# wordClock.net
KiCad netlist of a schematic drawn in EAGLE
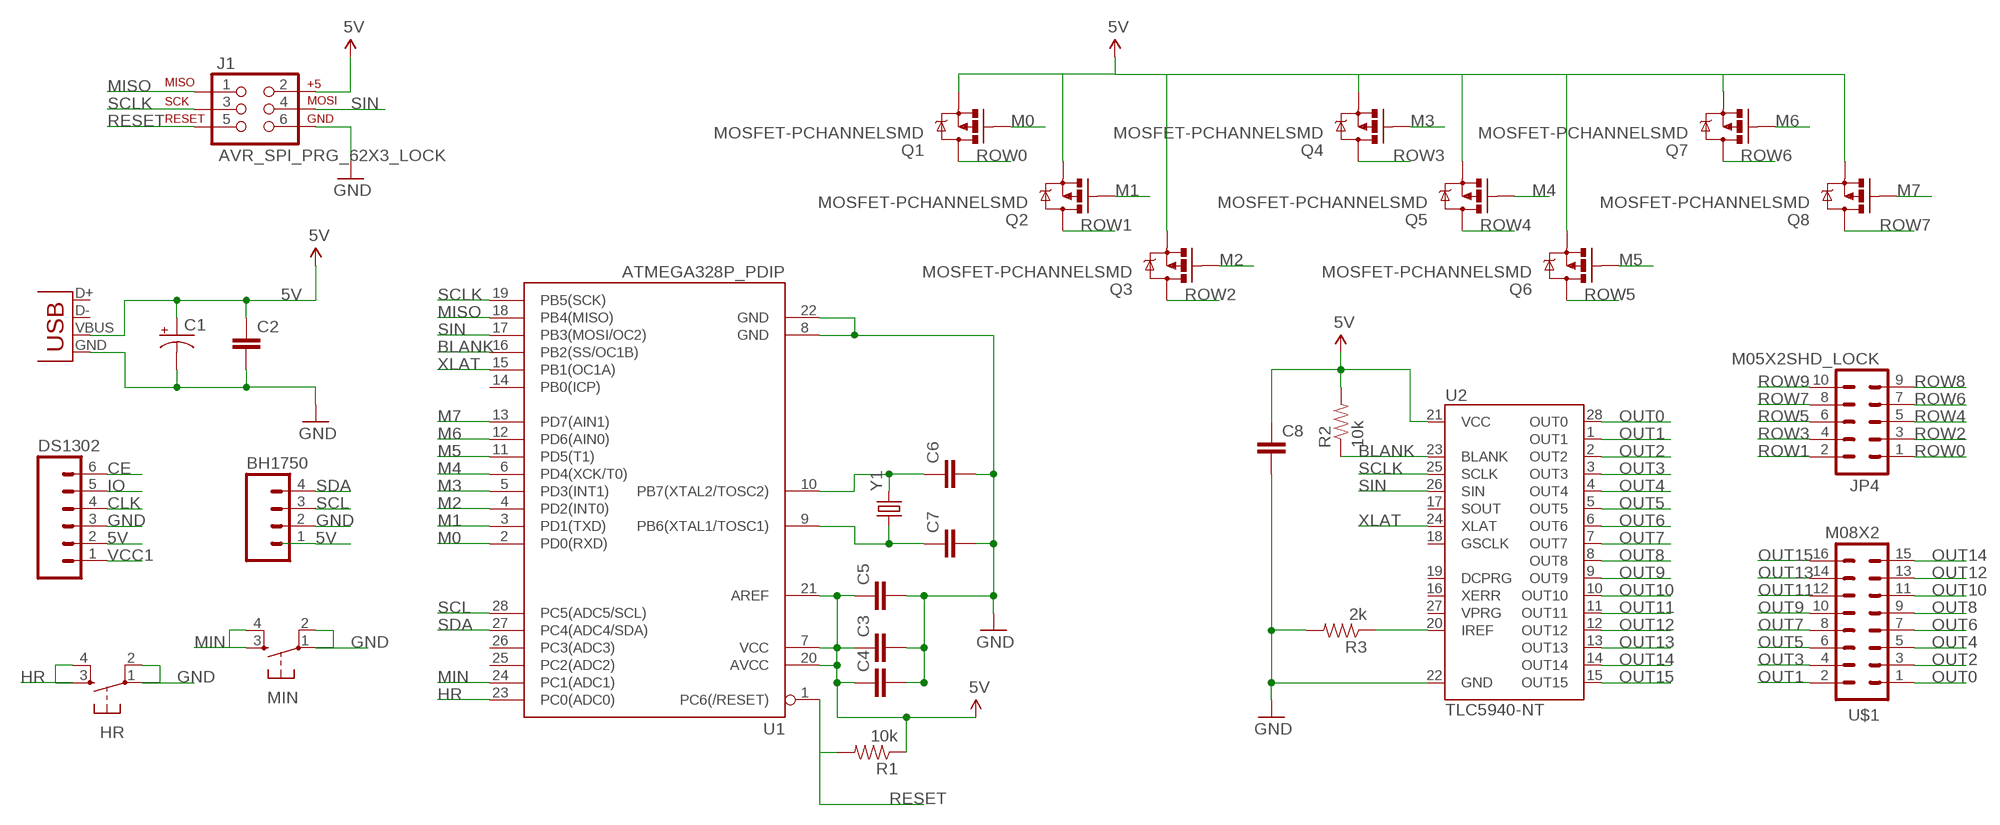
[diagram p0: schematic, sheet 1]

(export (version "E")
  (design (tool "Eeschema 10.0.6"))
  (components
    (comp (ref "BH1750")
      (value "M04LOCK")
      (footprint "eagle-import:1X04_LOCK")
      (libsource (lib "eagle-import") (part "M04LOCK"))
    )
    (comp (ref "C1")
      (value "CAP_POLD")
      (footprint "eagle-import:PANASONIC_D")
      (libsource (lib "eagle-import") (part "CAP_POLD"))
    )
    (comp (ref "C2")
      (value "CAP0805")
      (footprint "eagle-import:0805")
      (libsource (lib "eagle-import") (part "CAP0805"))
    )
    (comp (ref "C3")
      (value "CAP0805")
      (footprint "eagle-import:0805")
      (libsource (lib "eagle-import") (part "CAP0805"))
    )
    (comp (ref "C4")
      (value "CAP0805")
      (footprint "eagle-import:0805")
      (libsource (lib "eagle-import") (part "CAP0805"))
    )
    (comp (ref "C5")
      (value "CAP0805")
      (footprint "eagle-import:0805")
      (libsource (lib "eagle-import") (part "CAP0805"))
    )
    (comp (ref "C6")
      (value "CAP0805")
      (footprint "eagle-import:0805")
      (libsource (lib "eagle-import") (part "CAP0805"))
    )
    (comp (ref "C7")
      (value "CAP0805")
      (footprint "eagle-import:0805")
      (libsource (lib "eagle-import") (part "CAP0805"))
    )
    (comp (ref "C8")
      (value "CAP0805")
      (footprint "eagle-import:0805")
      (libsource (lib "eagle-import") (part "CAP0805"))
    )
    (comp (ref "DS1302")
      (value "M06LOCK")
      (footprint "eagle-import:1X06_LOCK")
      (libsource (lib "eagle-import") (part "M06LOCK"))
    )
    (comp (ref "HR")
      (value "TAC_SWITCHPTH")
      (footprint "eagle-import:TACTILE-PTH")
      (libsource (lib "eagle-import") (part "TAC_SWITCHPTH"))
    )
    (comp (ref "J1")
      (value "AVR_SPI_PRG_62X3_LOCK")
      (footprint "eagle-import:2X3_LOCK")
      (libsource (lib "eagle-import") (part "AVR_SPI_PRG_62X3_LOCK"))
    )
    (comp (ref "JP1")
      (value "USBPTH-VERTICAL")
      (footprint "eagle-import:USB-B-PTH-VERTICAL")
      (libsource (lib "eagle-import") (part "USBPTH-VERTICAL"))
    )
    (comp (ref "JP4")
      (value "M05X2SHD_LOCK")
      (footprint "eagle-import:2X5-SHROUDED_LOCK")
      (libsource (lib "eagle-import") (part "M05X2SHD_LOCK"))
    )
    (comp (ref "MIN")
      (value "TAC_SWITCHPTH")
      (footprint "eagle-import:TACTILE-PTH")
      (libsource (lib "eagle-import") (part "TAC_SWITCHPTH"))
    )
    (comp (ref "Q1")
      (value "MOSFET-PCHANNELSMD")
      (footprint "eagle-import:SOT23-3")
      (libsource (lib "eagle-import") (part "MOSFET-PCHANNELSMD"))
    )
    (comp (ref "Q2")
      (value "MOSFET-PCHANNELSMD")
      (footprint "eagle-import:SOT23-3")
      (libsource (lib "eagle-import") (part "MOSFET-PCHANNELSMD"))
    )
    (comp (ref "Q3")
      (value "MOSFET-PCHANNELSMD")
      (footprint "eagle-import:SOT23-3")
      (libsource (lib "eagle-import") (part "MOSFET-PCHANNELSMD"))
    )
    (comp (ref "Q4")
      (value "MOSFET-PCHANNELSMD")
      (footprint "eagle-import:SOT23-3")
      (libsource (lib "eagle-import") (part "MOSFET-PCHANNELSMD"))
    )
    (comp (ref "Q5")
      (value "MOSFET-PCHANNELSMD")
      (footprint "eagle-import:SOT23-3")
      (libsource (lib "eagle-import") (part "MOSFET-PCHANNELSMD"))
    )
    (comp (ref "Q6")
      (value "MOSFET-PCHANNELSMD")
      (footprint "eagle-import:SOT23-3")
      (libsource (lib "eagle-import") (part "MOSFET-PCHANNELSMD"))
    )
    (comp (ref "Q7")
      (value "MOSFET-PCHANNELSMD")
      (footprint "eagle-import:SOT23-3")
      (libsource (lib "eagle-import") (part "MOSFET-PCHANNELSMD"))
    )
    (comp (ref "Q8")
      (value "MOSFET-PCHANNELSMD")
      (footprint "eagle-import:SOT23-3")
      (libsource (lib "eagle-import") (part "MOSFET-PCHANNELSMD"))
    )
    (comp (ref "R1")
      (value "10k")
      (footprint "eagle-import:0805")
      (libsource (lib "eagle-import") (part "RESISTOR0805-RES"))
    )
    (comp (ref "R2")
      (value "10k")
      (footprint "eagle-import:0805")
      (libsource (lib "eagle-import") (part "RESISTOR0805-RES"))
    )
    (comp (ref "R3")
      (value "2k")
      (footprint "eagle-import:0805")
      (libsource (lib "eagle-import") (part "RESISTOR0805-RES"))
    )
    (comp (ref "U$1")
      (value "M08X2")
      (footprint "eagle-import:2X8")
      (libsource (lib "eagle-import") (part "M08X2"))
    )
    (comp (ref "U1")
      (value "ATMEGA328P_PDIP")
      (footprint "eagle-import:DIL28-3")
      (libsource (lib "eagle-import") (part "ATMEGA328P_PDIP"))
    )
    (comp (ref "U2")
      (value "TLC5940-NT")
      (footprint "eagle-import:DIL28-3")
      (libsource (lib "eagle-import") (part "TLC5940-NT"))
    )
    (comp (ref "Y1")
      (value "CRYSTALSMD")
      (footprint "eagle-import:HC49UP")
      (libsource (lib "eagle-import") (part "CRYSTALSMD"))
    )
  )
  (nets
    (net (code "1") (name "/BLANK") (class "Default")
      (node (ref "R2") (pin "1") (pinfunction "1_1") (pintype "passive"))
      (node (ref "U1") (pin "16") (pinfunction "PB2(SS/OC1B)_16") (pintype "bidirectional"))
      (node (ref "U2") (pin "23") (pinfunction "BLANK_23") (pintype "bidirectional"))
    )
    (net (code "2") (name "/CE") (class "Default")
      (node (ref "DS1302") (pin "6") (pinfunction "6_6") (pintype "passive"))
    )
    (net (code "3") (name "/CLK") (class "Default")
      (node (ref "DS1302") (pin "4") (pinfunction "4_4") (pintype "passive"))
    )
    (net (code "4") (name "/HR") (class "Default")
      (node (ref "HR") (pin "3") (pinfunction "3_3") (pintype "passive"))
      (node (ref "HR") (pin "4") (pinfunction "4_4") (pintype "passive"))
      (node (ref "U1") (pin "23") (pinfunction "PC0(ADC0)_23") (pintype "bidirectional"))
    )
    (net (code "5") (name "/IO") (class "Default")
      (node (ref "DS1302") (pin "5") (pinfunction "5_5") (pintype "passive"))
    )
    (net (code "6") (name "/M0") (class "Default")
      (node (ref "Q1") (pin "1") (pinfunction "G_1") (pintype "passive"))
      (node (ref "U1") (pin "2") (pinfunction "PD0(RXD)_2") (pintype "bidirectional"))
    )
    (net (code "7") (name "/M1") (class "Default")
      (node (ref "Q2") (pin "1") (pinfunction "G_1") (pintype "passive"))
      (node (ref "U1") (pin "3") (pinfunction "PD1(TXD)_3") (pintype "bidirectional"))
    )
    (net (code "8") (name "/M2") (class "Default")
      (node (ref "Q3") (pin "1") (pinfunction "G_1") (pintype "passive"))
      (node (ref "U1") (pin "4") (pinfunction "PD2(INT0)_4") (pintype "bidirectional"))
    )
    (net (code "9") (name "/M3") (class "Default")
      (node (ref "Q4") (pin "1") (pinfunction "G_1") (pintype "passive"))
      (node (ref "U1") (pin "5") (pinfunction "PD3(INT1)_5") (pintype "bidirectional"))
    )
    (net (code "10") (name "/M4") (class "Default")
      (node (ref "Q5") (pin "1") (pinfunction "G_1") (pintype "passive"))
      (node (ref "U1") (pin "6") (pinfunction "PD4(XCK/T0)_6") (pintype "bidirectional"))
    )
    (net (code "11") (name "/M5") (class "Default")
      (node (ref "Q6") (pin "1") (pinfunction "G_1") (pintype "passive"))
      (node (ref "U1") (pin "11") (pinfunction "PD5(T1)_11") (pintype "bidirectional"))
    )
    (net (code "12") (name "/M6") (class "Default")
      (node (ref "Q7") (pin "1") (pinfunction "G_1") (pintype "passive"))
      (node (ref "U1") (pin "12") (pinfunction "PD6(AIN0)_12") (pintype "bidirectional"))
    )
    (net (code "13") (name "/M7") (class "Default")
      (node (ref "Q8") (pin "1") (pinfunction "G_1") (pintype "passive"))
      (node (ref "U1") (pin "13") (pinfunction "PD7(AIN1)_13") (pintype "bidirectional"))
    )
    (net (code "14") (name "/MIN") (class "Default")
      (node (ref "MIN") (pin "3") (pinfunction "3_3") (pintype "passive"))
      (node (ref "MIN") (pin "4") (pinfunction "4_4") (pintype "passive"))
      (node (ref "U1") (pin "24") (pinfunction "PC1(ADC1)_24") (pintype "bidirectional"))
    )
    (net (code "15") (name "/MISO") (class "Default")
      (node (ref "J1") (pin "1") (pinfunction "1_1") (pintype "passive"))
      (node (ref "U1") (pin "18") (pinfunction "PB4(MISO)_18") (pintype "bidirectional"))
    )
    (net (code "16") (name "/OUT0") (class "Default")
      (node (ref "U$1") (pin "1") (pinfunction "1_1") (pintype "passive"))
      (node (ref "U2") (pin "28") (pinfunction "OUT0_28") (pintype "bidirectional"))
    )
    (net (code "17") (name "/OUT1") (class "Default")
      (node (ref "U$1") (pin "2") (pinfunction "2_2") (pintype "passive"))
      (node (ref "U2") (pin "1") (pinfunction "OUT1_1") (pintype "bidirectional"))
    )
    (net (code "18") (name "/OUT2") (class "Default")
      (node (ref "U$1") (pin "3") (pinfunction "3_3") (pintype "passive"))
      (node (ref "U2") (pin "2") (pinfunction "OUT2_2") (pintype "bidirectional"))
    )
    (net (code "19") (name "/OUT3") (class "Default")
      (node (ref "U$1") (pin "4") (pinfunction "4_4") (pintype "passive"))
      (node (ref "U2") (pin "3") (pinfunction "OUT3_3") (pintype "bidirectional"))
    )
    (net (code "20") (name "/OUT4") (class "Default")
      (node (ref "U$1") (pin "5") (pinfunction "5_5") (pintype "passive"))
      (node (ref "U2") (pin "4") (pinfunction "OUT4_4") (pintype "bidirectional"))
    )
    (net (code "21") (name "/OUT5") (class "Default")
      (node (ref "U$1") (pin "6") (pinfunction "6_6") (pintype "passive"))
      (node (ref "U2") (pin "5") (pinfunction "OUT5_5") (pintype "bidirectional"))
    )
    (net (code "22") (name "/OUT6") (class "Default")
      (node (ref "U$1") (pin "7") (pinfunction "7_7") (pintype "passive"))
      (node (ref "U2") (pin "6") (pinfunction "OUT6_6") (pintype "bidirectional"))
    )
    (net (code "23") (name "/OUT7") (class "Default")
      (node (ref "U$1") (pin "8") (pinfunction "8_8") (pintype "passive"))
      (node (ref "U2") (pin "7") (pinfunction "OUT7_7") (pintype "bidirectional"))
    )
    (net (code "24") (name "/OUT8") (class "Default")
      (node (ref "U$1") (pin "9") (pinfunction "9_9") (pintype "passive"))
      (node (ref "U2") (pin "8") (pinfunction "OUT8_8") (pintype "bidirectional"))
    )
    (net (code "25") (name "/OUT9") (class "Default")
      (node (ref "U$1") (pin "10") (pinfunction "10_10") (pintype "passive"))
      (node (ref "U2") (pin "9") (pinfunction "OUT9_9") (pintype "bidirectional"))
    )
    (net (code "26") (name "/OUT10") (class "Default")
      (node (ref "U$1") (pin "11") (pinfunction "11_11") (pintype "passive"))
      (node (ref "U2") (pin "10") (pinfunction "OUT10_10") (pintype "bidirectional"))
    )
    (net (code "27") (name "/OUT11") (class "Default")
      (node (ref "U$1") (pin "12") (pinfunction "12_12") (pintype "passive"))
      (node (ref "U2") (pin "11") (pinfunction "OUT11_11") (pintype "bidirectional"))
    )
    (net (code "28") (name "/OUT12") (class "Default")
      (node (ref "U$1") (pin "13") (pinfunction "13_13") (pintype "passive"))
      (node (ref "U2") (pin "12") (pinfunction "OUT12_12") (pintype "bidirectional"))
    )
    (net (code "29") (name "/OUT13") (class "Default")
      (node (ref "U$1") (pin "14") (pinfunction "14_14") (pintype "passive"))
      (node (ref "U2") (pin "13") (pinfunction "OUT13_13") (pintype "bidirectional"))
    )
    (net (code "30") (name "/OUT14") (class "Default")
      (node (ref "U$1") (pin "15") (pinfunction "15_15") (pintype "passive"))
      (node (ref "U2") (pin "14") (pinfunction "OUT14_14") (pintype "bidirectional"))
    )
    (net (code "31") (name "/OUT15") (class "Default")
      (node (ref "U$1") (pin "16") (pinfunction "16_16") (pintype "passive"))
      (node (ref "U2") (pin "15") (pinfunction "OUT15_15") (pintype "bidirectional"))
    )
    (net (code "32") (name "/RESET") (class "Default")
      (node (ref "J1") (pin "5") (pinfunction "5_5") (pintype "passive"))
      (node (ref "R1") (pin "2") (pinfunction "2_2") (pintype "passive"))
      (node (ref "U1") (pin "1") (pinfunction "PC6(/RESET)_1") (pintype "bidirectional"))
    )
    (net (code "33") (name "/ROW0") (class "Default")
      (node (ref "JP4") (pin "1") (pinfunction "1_1") (pintype "passive"))
      (node (ref "Q1") (pin "3") (pinfunction "D_3") (pintype "passive"))
    )
    (net (code "34") (name "/ROW1") (class "Default")
      (node (ref "JP4") (pin "2") (pinfunction "2_2") (pintype "passive"))
      (node (ref "Q2") (pin "3") (pinfunction "D_3") (pintype "passive"))
    )
    (net (code "35") (name "/ROW2") (class "Default")
      (node (ref "JP4") (pin "3") (pinfunction "3_3") (pintype "passive"))
      (node (ref "Q3") (pin "3") (pinfunction "D_3") (pintype "passive"))
    )
    (net (code "36") (name "/ROW3") (class "Default")
      (node (ref "JP4") (pin "4") (pinfunction "4_4") (pintype "passive"))
      (node (ref "Q4") (pin "3") (pinfunction "D_3") (pintype "passive"))
    )
    (net (code "37") (name "/ROW4") (class "Default")
      (node (ref "JP4") (pin "5") (pinfunction "5_5") (pintype "passive"))
      (node (ref "Q5") (pin "3") (pinfunction "D_3") (pintype "passive"))
    )
    (net (code "38") (name "/ROW5") (class "Default")
      (node (ref "JP4") (pin "6") (pinfunction "6_6") (pintype "passive"))
      (node (ref "Q6") (pin "3") (pinfunction "D_3") (pintype "passive"))
    )
    (net (code "39") (name "/ROW6") (class "Default")
      (node (ref "JP4") (pin "7") (pinfunction "7_7") (pintype "passive"))
      (node (ref "Q7") (pin "3") (pinfunction "D_3") (pintype "passive"))
    )
    (net (code "40") (name "/ROW7") (class "Default")
      (node (ref "JP4") (pin "8") (pinfunction "8_8") (pintype "passive"))
      (node (ref "Q8") (pin "3") (pinfunction "D_3") (pintype "passive"))
    )
    (net (code "41") (name "/ROW8") (class "Default")
      (node (ref "JP4") (pin "9") (pinfunction "9_9") (pintype "passive"))
    )
    (net (code "42") (name "/ROW9") (class "Default")
      (node (ref "JP4") (pin "10") (pinfunction "10_10") (pintype "passive"))
    )
    (net (code "43") (name "/SCL") (class "Default")
      (node (ref "BH1750") (pin "3") (pinfunction "3_3") (pintype "passive"))
      (node (ref "U1") (pin "28") (pinfunction "PC5(ADC5/SCL)_28") (pintype "bidirectional"))
    )
    (net (code "44") (name "/SCLK") (class "Default")
      (node (ref "J1") (pin "3") (pinfunction "3_3") (pintype "passive"))
      (node (ref "U1") (pin "19") (pinfunction "PB5(SCK)_19") (pintype "bidirectional"))
      (node (ref "U2") (pin "25") (pinfunction "SCLK_25") (pintype "bidirectional"))
    )
    (net (code "45") (name "/SDA") (class "Default")
      (node (ref "BH1750") (pin "4") (pinfunction "4_4") (pintype "passive"))
      (node (ref "U1") (pin "27") (pinfunction "PC4(ADC4/SDA)_27") (pintype "bidirectional"))
    )
    (net (code "46") (name "/SIN") (class "Default")
      (node (ref "J1") (pin "4") (pinfunction "4_4") (pintype "passive"))
      (node (ref "U1") (pin "17") (pinfunction "PB3(MOSI/OC2)_17") (pintype "bidirectional"))
      (node (ref "U2") (pin "26") (pinfunction "SIN_26") (pintype "bidirectional"))
    )
    (net (code "47") (name "/VCC1") (class "Default")
      (node (ref "DS1302") (pin "1") (pinfunction "1_1") (pintype "passive"))
    )
    (net (code "48") (name "/XLAT") (class "Default")
      (node (ref "U1") (pin "15") (pinfunction "PB1(OC1A)_15") (pintype "bidirectional"))
      (node (ref "U2") (pin "24") (pinfunction "XLAT_24") (pintype "bidirectional"))
    )
    (net (code "49") (name "5V") (class "Default")
      (node (ref "BH1750") (pin "1") (pinfunction "1_1") (pintype "passive"))
      (node (ref "C1") (pin "+") (pinfunction "+_+") (pintype "passive"))
      (node (ref "C2") (pin "1") (pinfunction "1_1") (pintype "passive"))
      (node (ref "C3") (pin "1") (pinfunction "1_1") (pintype "passive"))
      (node (ref "C4") (pin "1") (pinfunction "1_1") (pintype "passive"))
      (node (ref "C5") (pin "1") (pinfunction "1_1") (pintype "passive"))
      (node (ref "C8") (pin "1") (pinfunction "1_1") (pintype "passive"))
      (node (ref "DS1302") (pin "2") (pinfunction "2_2") (pintype "passive"))
      (node (ref "J1") (pin "2") (pinfunction "2_2") (pintype "passive"))
      (node (ref "JP1") (pin "VBUS") (pinfunction "VBUS_VBUS") (pintype "bidirectional"))
      (node (ref "Q1") (pin "2") (pinfunction "S_2") (pintype "passive"))
      (node (ref "Q2") (pin "2") (pinfunction "S_2") (pintype "passive"))
      (node (ref "Q3") (pin "2") (pinfunction "S_2") (pintype "passive"))
      (node (ref "Q4") (pin "2") (pinfunction "S_2") (pintype "passive"))
      (node (ref "Q5") (pin "2") (pinfunction "S_2") (pintype "passive"))
      (node (ref "Q6") (pin "2") (pinfunction "S_2") (pintype "passive"))
      (node (ref "Q7") (pin "2") (pinfunction "S_2") (pintype "passive"))
      (node (ref "Q8") (pin "2") (pinfunction "S_2") (pintype "passive"))
      (node (ref "R1") (pin "1") (pinfunction "1_1") (pintype "passive"))
      (node (ref "R2") (pin "2") (pinfunction "2_2") (pintype "passive"))
      (node (ref "U1") (pin "20") (pinfunction "AVCC_20") (pintype "bidirectional"))
      (node (ref "U1") (pin "21") (pinfunction "AREF_21") (pintype "bidirectional"))
      (node (ref "U1") (pin "7") (pinfunction "VCC_7") (pintype "bidirectional"))
      (node (ref "U2") (pin "21") (pinfunction "VCC_21") (pintype "bidirectional"))
    )
    (net (code "50") (name "GND") (class "Default")
      (node (ref "BH1750") (pin "2") (pinfunction "2_2") (pintype "passive"))
      (node (ref "C1") (pin "-") (pinfunction "-_-") (pintype "passive"))
      (node (ref "C2") (pin "2") (pinfunction "2_2") (pintype "passive"))
      (node (ref "C3") (pin "2") (pinfunction "2_2") (pintype "passive"))
      (node (ref "C4") (pin "2") (pinfunction "2_2") (pintype "passive"))
      (node (ref "C5") (pin "2") (pinfunction "2_2") (pintype "passive"))
      (node (ref "C6") (pin "2") (pinfunction "2_2") (pintype "passive"))
      (node (ref "C7") (pin "2") (pinfunction "2_2") (pintype "passive"))
      (node (ref "C8") (pin "2") (pinfunction "2_2") (pintype "passive"))
      (node (ref "DS1302") (pin "3") (pinfunction "3_3") (pintype "passive"))
      (node (ref "HR") (pin "1") (pinfunction "1_1") (pintype "passive"))
      (node (ref "HR") (pin "2") (pinfunction "2_2") (pintype "passive"))
      (node (ref "J1") (pin "6") (pinfunction "6_6") (pintype "passive"))
      (node (ref "JP1") (pin "GND") (pinfunction "GND_GND") (pintype "bidirectional"))
      (node (ref "MIN") (pin "1") (pinfunction "1_1") (pintype "passive"))
      (node (ref "MIN") (pin "2") (pinfunction "2_2") (pintype "passive"))
      (node (ref "R3") (pin "2") (pinfunction "2_2") (pintype "passive"))
      (node (ref "U1") (pin "22") (pinfunction "GND_22") (pintype "bidirectional"))
      (node (ref "U1") (pin "8") (pinfunction "GND_8") (pintype "bidirectional"))
      (node (ref "U2") (pin "22") (pinfunction "GND_22") (pintype "bidirectional"))
    )
    (net (code "51") (name "Net-(U1-PB6(XTAL1{slash}TOSC1))") (class "Default")
      (node (ref "C7") (pin "1") (pinfunction "1_1") (pintype "passive"))
      (node (ref "U1") (pin "9") (pinfunction "PB6(XTAL1/TOSC1)_9") (pintype "bidirectional"))
      (node (ref "Y1") (pin "1") (pinfunction "1_1") (pintype "passive"))
    )
    (net (code "52") (name "Net-(U1-PB7(XTAL2{slash}TOSC2))") (class "Default")
      (node (ref "C6") (pin "1") (pinfunction "1_1") (pintype "passive"))
      (node (ref "U1") (pin "10") (pinfunction "PB7(XTAL2/TOSC2)_10") (pintype "bidirectional"))
      (node (ref "Y1") (pin "2") (pinfunction "2_2") (pintype "passive"))
    )
    (net (code "53") (name "Net-(U2-IREF)") (class "Default")
      (node (ref "R3") (pin "1") (pinfunction "1_1") (pintype "passive"))
      (node (ref "U2") (pin "20") (pinfunction "IREF_20") (pintype "bidirectional"))
    )
    (net (code "54") (name "unconnected-(JP1-PadD+)") (class "Default")
      (node (ref "JP1") (pin "D+") (pinfunction "D+_D+") (pintype "bidirectional"))
    )
    (net (code "55") (name "unconnected-(JP1-PadD-)") (class "Default")
      (node (ref "JP1") (pin "D-") (pinfunction "D-_D-") (pintype "bidirectional"))
    )
    (net (code "56") (name "unconnected-(U1-PB0(ICP)-Pad14)") (class "Default")
      (node (ref "U1") (pin "14") (pinfunction "PB0(ICP)_14") (pintype "bidirectional"))
    )
    (net (code "57") (name "unconnected-(U1-PC2(ADC2)-Pad25)") (class "Default")
      (node (ref "U1") (pin "25") (pinfunction "PC2(ADC2)_25") (pintype "bidirectional"))
    )
    (net (code "58") (name "unconnected-(U1-PC3(ADC3)-Pad26)") (class "Default")
      (node (ref "U1") (pin "26") (pinfunction "PC3(ADC3)_26") (pintype "bidirectional"))
    )
    (net (code "59") (name "unconnected-(U2-DCPRG-Pad19)") (class "Default")
      (node (ref "U2") (pin "19") (pinfunction "DCPRG_19") (pintype "bidirectional"))
    )
    (net (code "60") (name "unconnected-(U2-GSCLK-Pad18)") (class "Default")
      (node (ref "U2") (pin "18") (pinfunction "GSCLK_18") (pintype "bidirectional"))
    )
    (net (code "61") (name "unconnected-(U2-SOUT-Pad17)") (class "Default")
      (node (ref "U2") (pin "17") (pinfunction "SOUT_17") (pintype "bidirectional"))
    )
    (net (code "62") (name "unconnected-(U2-VPRG-Pad27)") (class "Default")
      (node (ref "U2") (pin "27") (pinfunction "VPRG_27") (pintype "bidirectional"))
    )
    (net (code "63") (name "unconnected-(U2-XERR-Pad16)") (class "Default")
      (node (ref "U2") (pin "16") (pinfunction "XERR_16") (pintype "bidirectional"))
    )
  )
)
